# SCH_PCB-Final_2025-01-21.net
KiCad netlist of a schematic drawn in EasyEDA
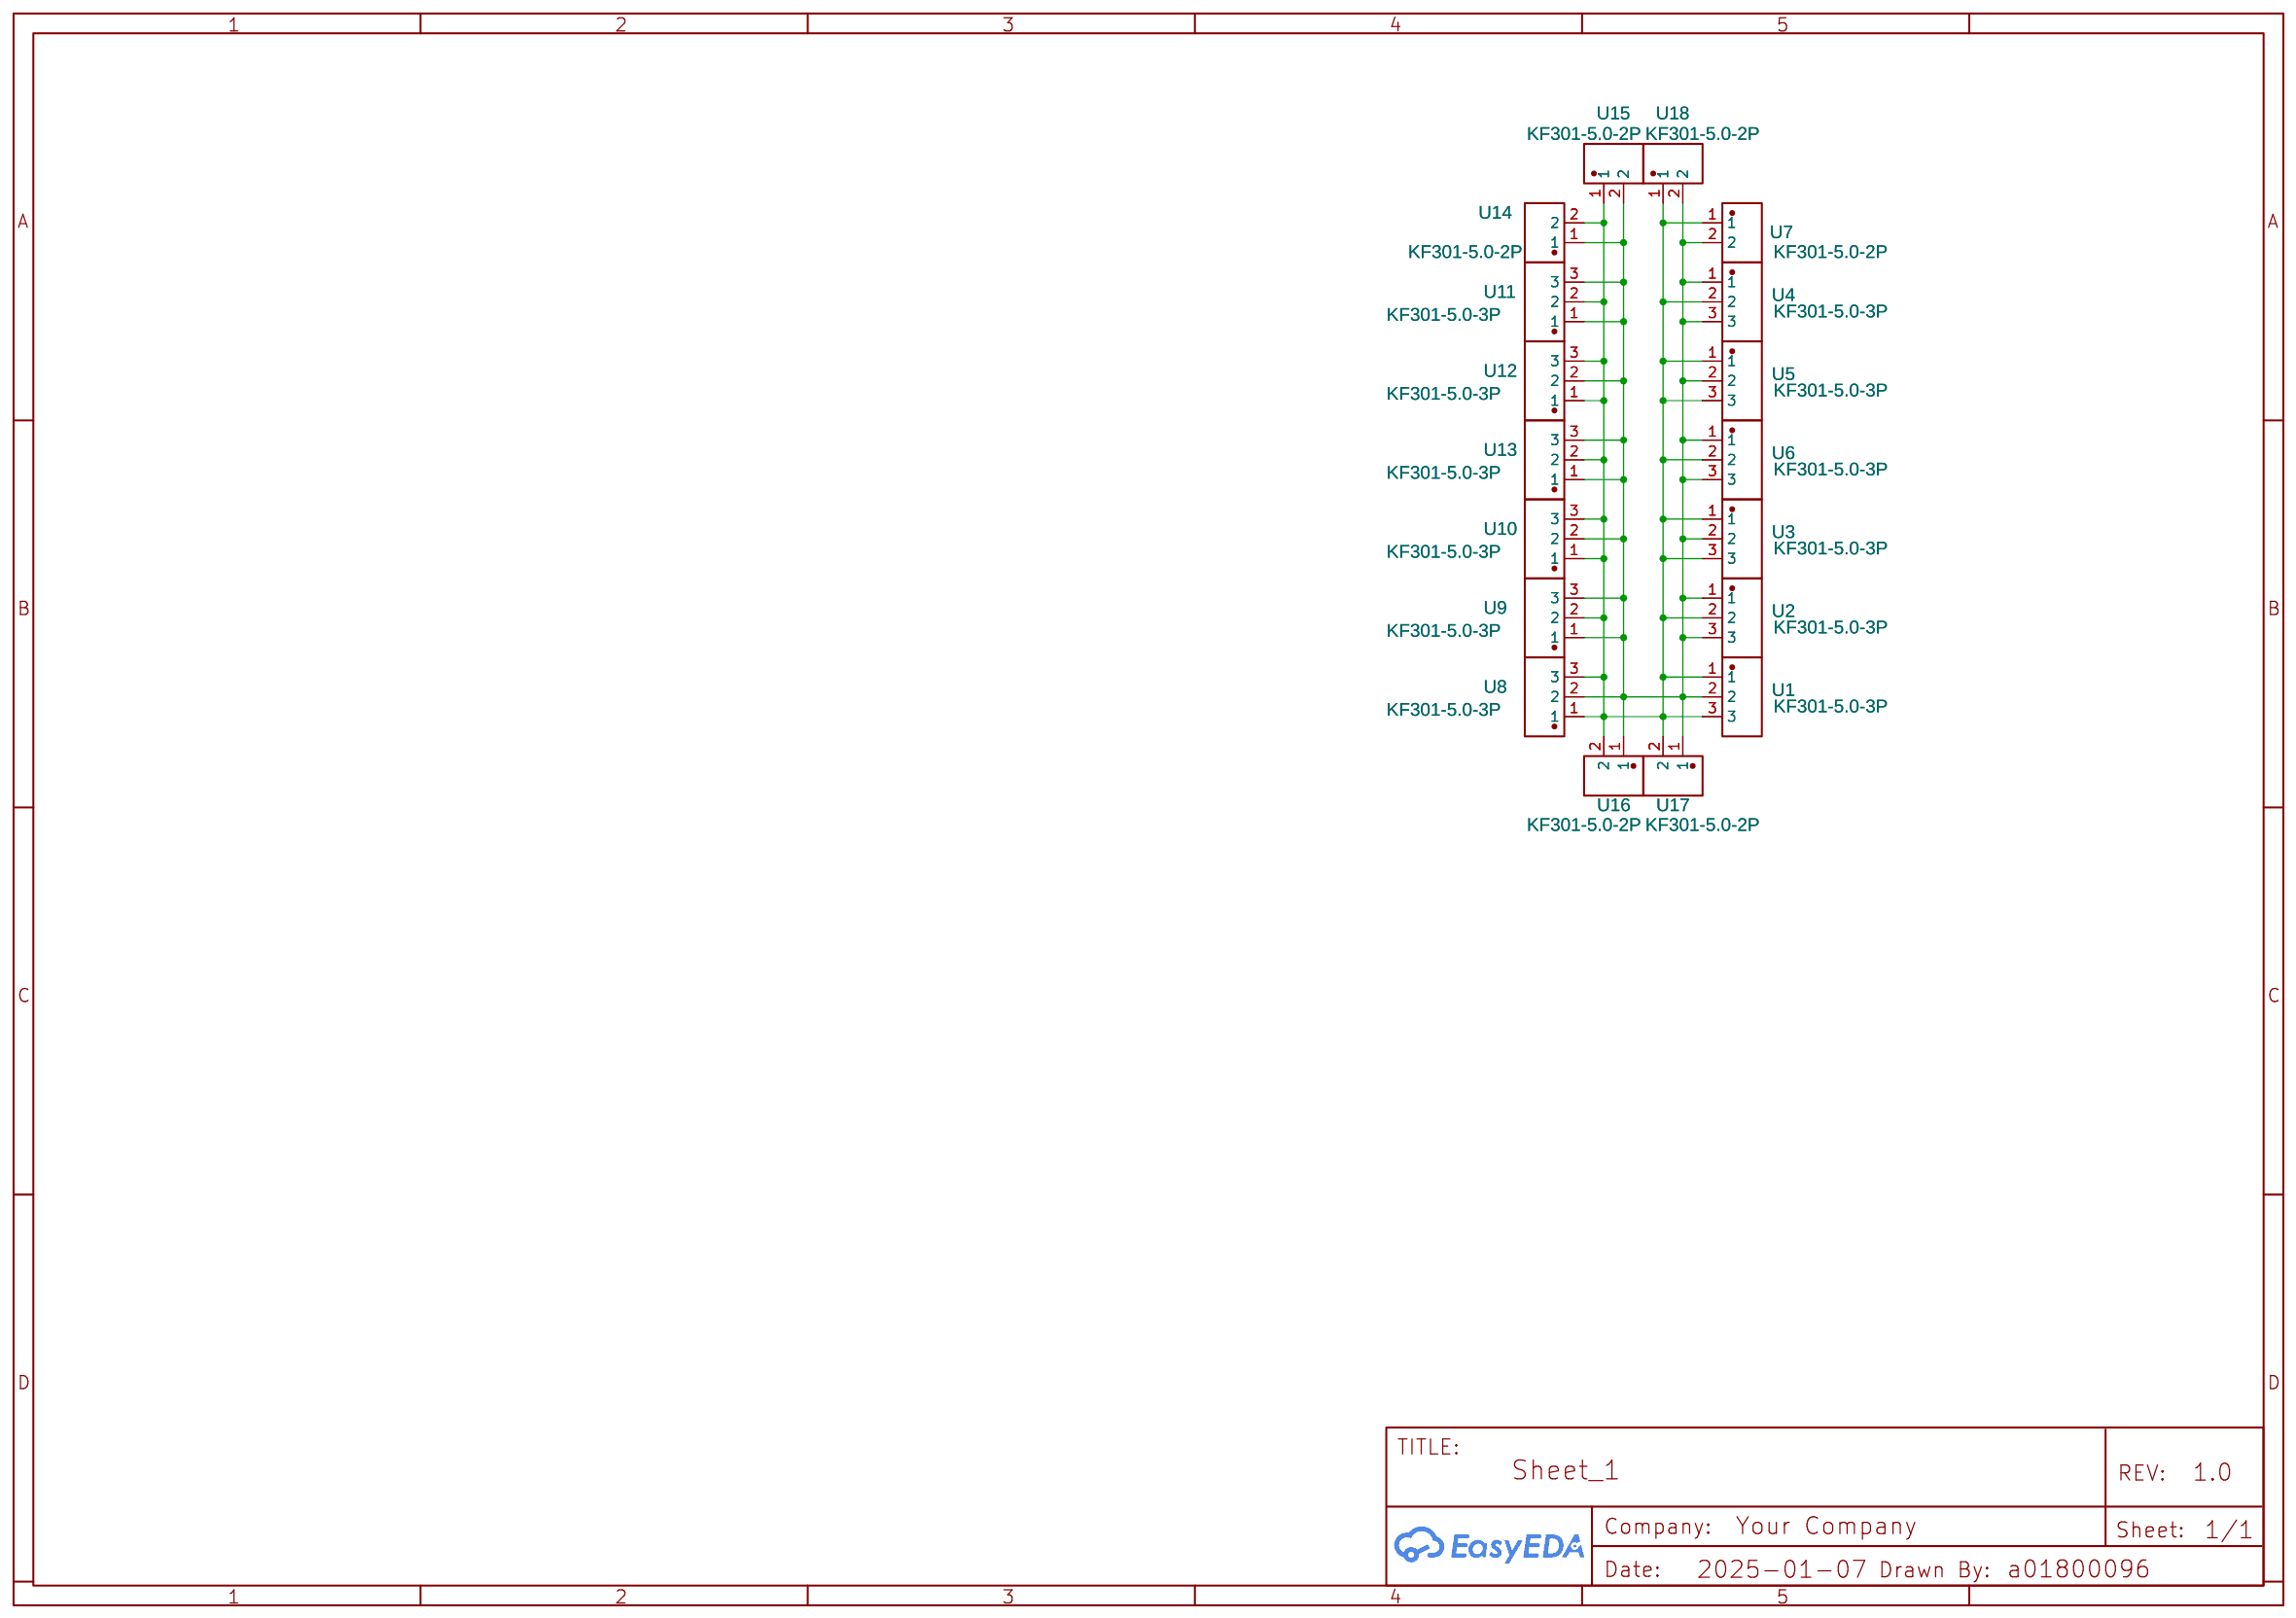
[diagram p0: schematic sheet]

(export (version "E")
  (design (tool "Eeschema 10.0.6"))
  (components
    (comp (ref "U1")
      (value "KF301-5.0-3P")
      (fields (field (name "Manufacturer") "KEFA(科发)"))
      (libsource (lib "") (part "KF301-5.0-3P"))
    )
    (comp (ref "U2")
      (value "KF301-5.0-3P")
      (fields (field (name "Manufacturer") "KEFA(科发)"))
      (libsource (lib "") (part "KF301-5.0-3P"))
    )
    (comp (ref "U3")
      (value "KF301-5.0-3P")
      (fields (field (name "Manufacturer") "KEFA(科发)"))
      (libsource (lib "") (part "KF301-5.0-3P"))
    )
    (comp (ref "U4")
      (value "KF301-5.0-3P")
      (fields (field (name "Manufacturer") "KEFA(科发)"))
      (libsource (lib "") (part "KF301-5.0-3P"))
    )
    (comp (ref "U5")
      (value "KF301-5.0-3P")
      (fields (field (name "Manufacturer") "KEFA(科发)"))
      (libsource (lib "") (part "KF301-5.0-3P"))
    )
    (comp (ref "U6")
      (value "KF301-5.0-3P")
      (fields (field (name "Manufacturer") "KEFA(科发)"))
      (libsource (lib "") (part "KF301-5.0-3P"))
    )
    (comp (ref "U7")
      (value "KF301-5.0-2P")
      (fields (field (name "Manufacturer") "KEFA(科发)"))
      (libsource (lib "") (part "KF301-5.0-2P_3"))
    )
    (comp (ref "U8")
      (value "KF301-5.0-3P")
      (fields (field (name "Manufacturer") "KEFA(科发)"))
      (libsource (lib "") (part "KF301-5.0-3P_1"))
    )
    (comp (ref "U9")
      (value "KF301-5.0-3P")
      (fields (field (name "Manufacturer") "KEFA(科发)"))
      (libsource (lib "") (part "KF301-5.0-3P_1"))
    )
    (comp (ref "U10")
      (value "KF301-5.0-3P")
      (fields (field (name "Manufacturer") "KEFA(科发)"))
      (libsource (lib "") (part "KF301-5.0-3P_1"))
    )
    (comp (ref "U11")
      (value "KF301-5.0-3P")
      (fields (field (name "Manufacturer") "KEFA(科发)"))
      (libsource (lib "") (part "KF301-5.0-3P_1"))
    )
    (comp (ref "U12")
      (value "KF301-5.0-3P")
      (fields (field (name "Manufacturer") "KEFA(科发)"))
      (libsource (lib "") (part "KF301-5.0-3P_1"))
    )
    (comp (ref "U13")
      (value "KF301-5.0-3P")
      (fields (field (name "Manufacturer") "KEFA(科发)"))
      (libsource (lib "") (part "KF301-5.0-3P_1"))
    )
    (comp (ref "U14")
      (value "KF301-5.0-2P")
      (fields (field (name "Manufacturer") "KEFA(科发)"))
      (libsource (lib "") (part "KF301-5.0-2P_2"))
    )
    (comp (ref "U15")
      (value "KF301-5.0-2P")
      (fields (field (name "Manufacturer") "KEFA(科发)"))
      (libsource (lib "") (part "KF301-5.0-2P_1"))
    )
    (comp (ref "U16")
      (value "KF301-5.0-2P")
      (fields (field (name "Manufacturer") "KEFA(科发)"))
      (libsource (lib "") (part "KF301-5.0-2P"))
    )
    (comp (ref "U17")
      (value "KF301-5.0-2P")
      (fields (field (name "Manufacturer") "KEFA(科发)"))
      (libsource (lib "") (part "KF301-5.0-2P"))
    )
    (comp (ref "U18")
      (value "KF301-5.0-2P")
      (fields (field (name "Manufacturer") "KEFA(科发)"))
      (libsource (lib "") (part "KF301-5.0-2P_1"))
    )
  )
  (nets
    (net (code "1") (name "Net-(U1-Pad1)") (class "Default")
      (node (ref "U1") (pin "1") (pinfunction "1_1") (pintype "unspecified"))
      (node (ref "U1") (pin "3") (pinfunction "3_3") (pintype "unspecified"))
      (node (ref "U10") (pin "1") (pinfunction "1_1") (pintype "unspecified"))
      (node (ref "U10") (pin "3") (pinfunction "3_3") (pintype "unspecified"))
      (node (ref "U11") (pin "2") (pinfunction "2_2") (pintype "unspecified"))
      (node (ref "U12") (pin "1") (pinfunction "1_1") (pintype "unspecified"))
      (node (ref "U12") (pin "3") (pinfunction "3_3") (pintype "unspecified"))
      (node (ref "U13") (pin "2") (pinfunction "2_2") (pintype "unspecified"))
      (node (ref "U14") (pin "2") (pinfunction "2_2") (pintype "unspecified"))
      (node (ref "U15") (pin "1") (pinfunction "1_1") (pintype "unspecified"))
      (node (ref "U16") (pin "2") (pinfunction "2_2") (pintype "unspecified"))
      (node (ref "U17") (pin "2") (pinfunction "2_2") (pintype "unspecified"))
      (node (ref "U18") (pin "1") (pinfunction "1_1") (pintype "unspecified"))
      (node (ref "U2") (pin "2") (pinfunction "2_2") (pintype "unspecified"))
      (node (ref "U3") (pin "1") (pinfunction "1_1") (pintype "unspecified"))
      (node (ref "U3") (pin "3") (pinfunction "3_3") (pintype "unspecified"))
      (node (ref "U4") (pin "2") (pinfunction "2_2") (pintype "unspecified"))
      (node (ref "U5") (pin "1") (pinfunction "1_1") (pintype "unspecified"))
      (node (ref "U5") (pin "3") (pinfunction "3_3") (pintype "unspecified"))
      (node (ref "U6") (pin "2") (pinfunction "2_2") (pintype "unspecified"))
      (node (ref "U7") (pin "1") (pinfunction "1_1") (pintype "unspecified"))
      (node (ref "U8") (pin "1") (pinfunction "1_1") (pintype "unspecified"))
      (node (ref "U8") (pin "3") (pinfunction "3_3") (pintype "unspecified"))
      (node (ref "U9") (pin "2") (pinfunction "2_2") (pintype "unspecified"))
    )
    (net (code "2") (name "Net-(U1-Pad2)") (class "Default")
      (node (ref "U1") (pin "2") (pinfunction "2_2") (pintype "unspecified"))
      (node (ref "U10") (pin "2") (pinfunction "2_2") (pintype "unspecified"))
      (node (ref "U11") (pin "1") (pinfunction "1_1") (pintype "unspecified"))
      (node (ref "U11") (pin "3") (pinfunction "3_3") (pintype "unspecified"))
      (node (ref "U12") (pin "2") (pinfunction "2_2") (pintype "unspecified"))
      (node (ref "U13") (pin "1") (pinfunction "1_1") (pintype "unspecified"))
      (node (ref "U13") (pin "3") (pinfunction "3_3") (pintype "unspecified"))
      (node (ref "U14") (pin "1") (pinfunction "1_1") (pintype "unspecified"))
      (node (ref "U15") (pin "2") (pinfunction "2_2") (pintype "unspecified"))
      (node (ref "U16") (pin "1") (pinfunction "1_1") (pintype "unspecified"))
      (node (ref "U17") (pin "1") (pinfunction "1_1") (pintype "unspecified"))
      (node (ref "U18") (pin "2") (pinfunction "2_2") (pintype "unspecified"))
      (node (ref "U2") (pin "1") (pinfunction "1_1") (pintype "unspecified"))
      (node (ref "U2") (pin "3") (pinfunction "3_3") (pintype "unspecified"))
      (node (ref "U3") (pin "2") (pinfunction "2_2") (pintype "unspecified"))
      (node (ref "U4") (pin "1") (pinfunction "1_1") (pintype "unspecified"))
      (node (ref "U4") (pin "3") (pinfunction "3_3") (pintype "unspecified"))
      (node (ref "U5") (pin "2") (pinfunction "2_2") (pintype "unspecified"))
      (node (ref "U6") (pin "1") (pinfunction "1_1") (pintype "unspecified"))
      (node (ref "U6") (pin "3") (pinfunction "3_3") (pintype "unspecified"))
      (node (ref "U7") (pin "2") (pinfunction "2_2") (pintype "unspecified"))
      (node (ref "U8") (pin "2") (pinfunction "2_2") (pintype "unspecified"))
      (node (ref "U9") (pin "1") (pinfunction "1_1") (pintype "unspecified"))
      (node (ref "U9") (pin "3") (pinfunction "3_3") (pintype "unspecified"))
    )
  )
)
